# Power.net
KiCad netlist of a schematic drawn in Altium Designer
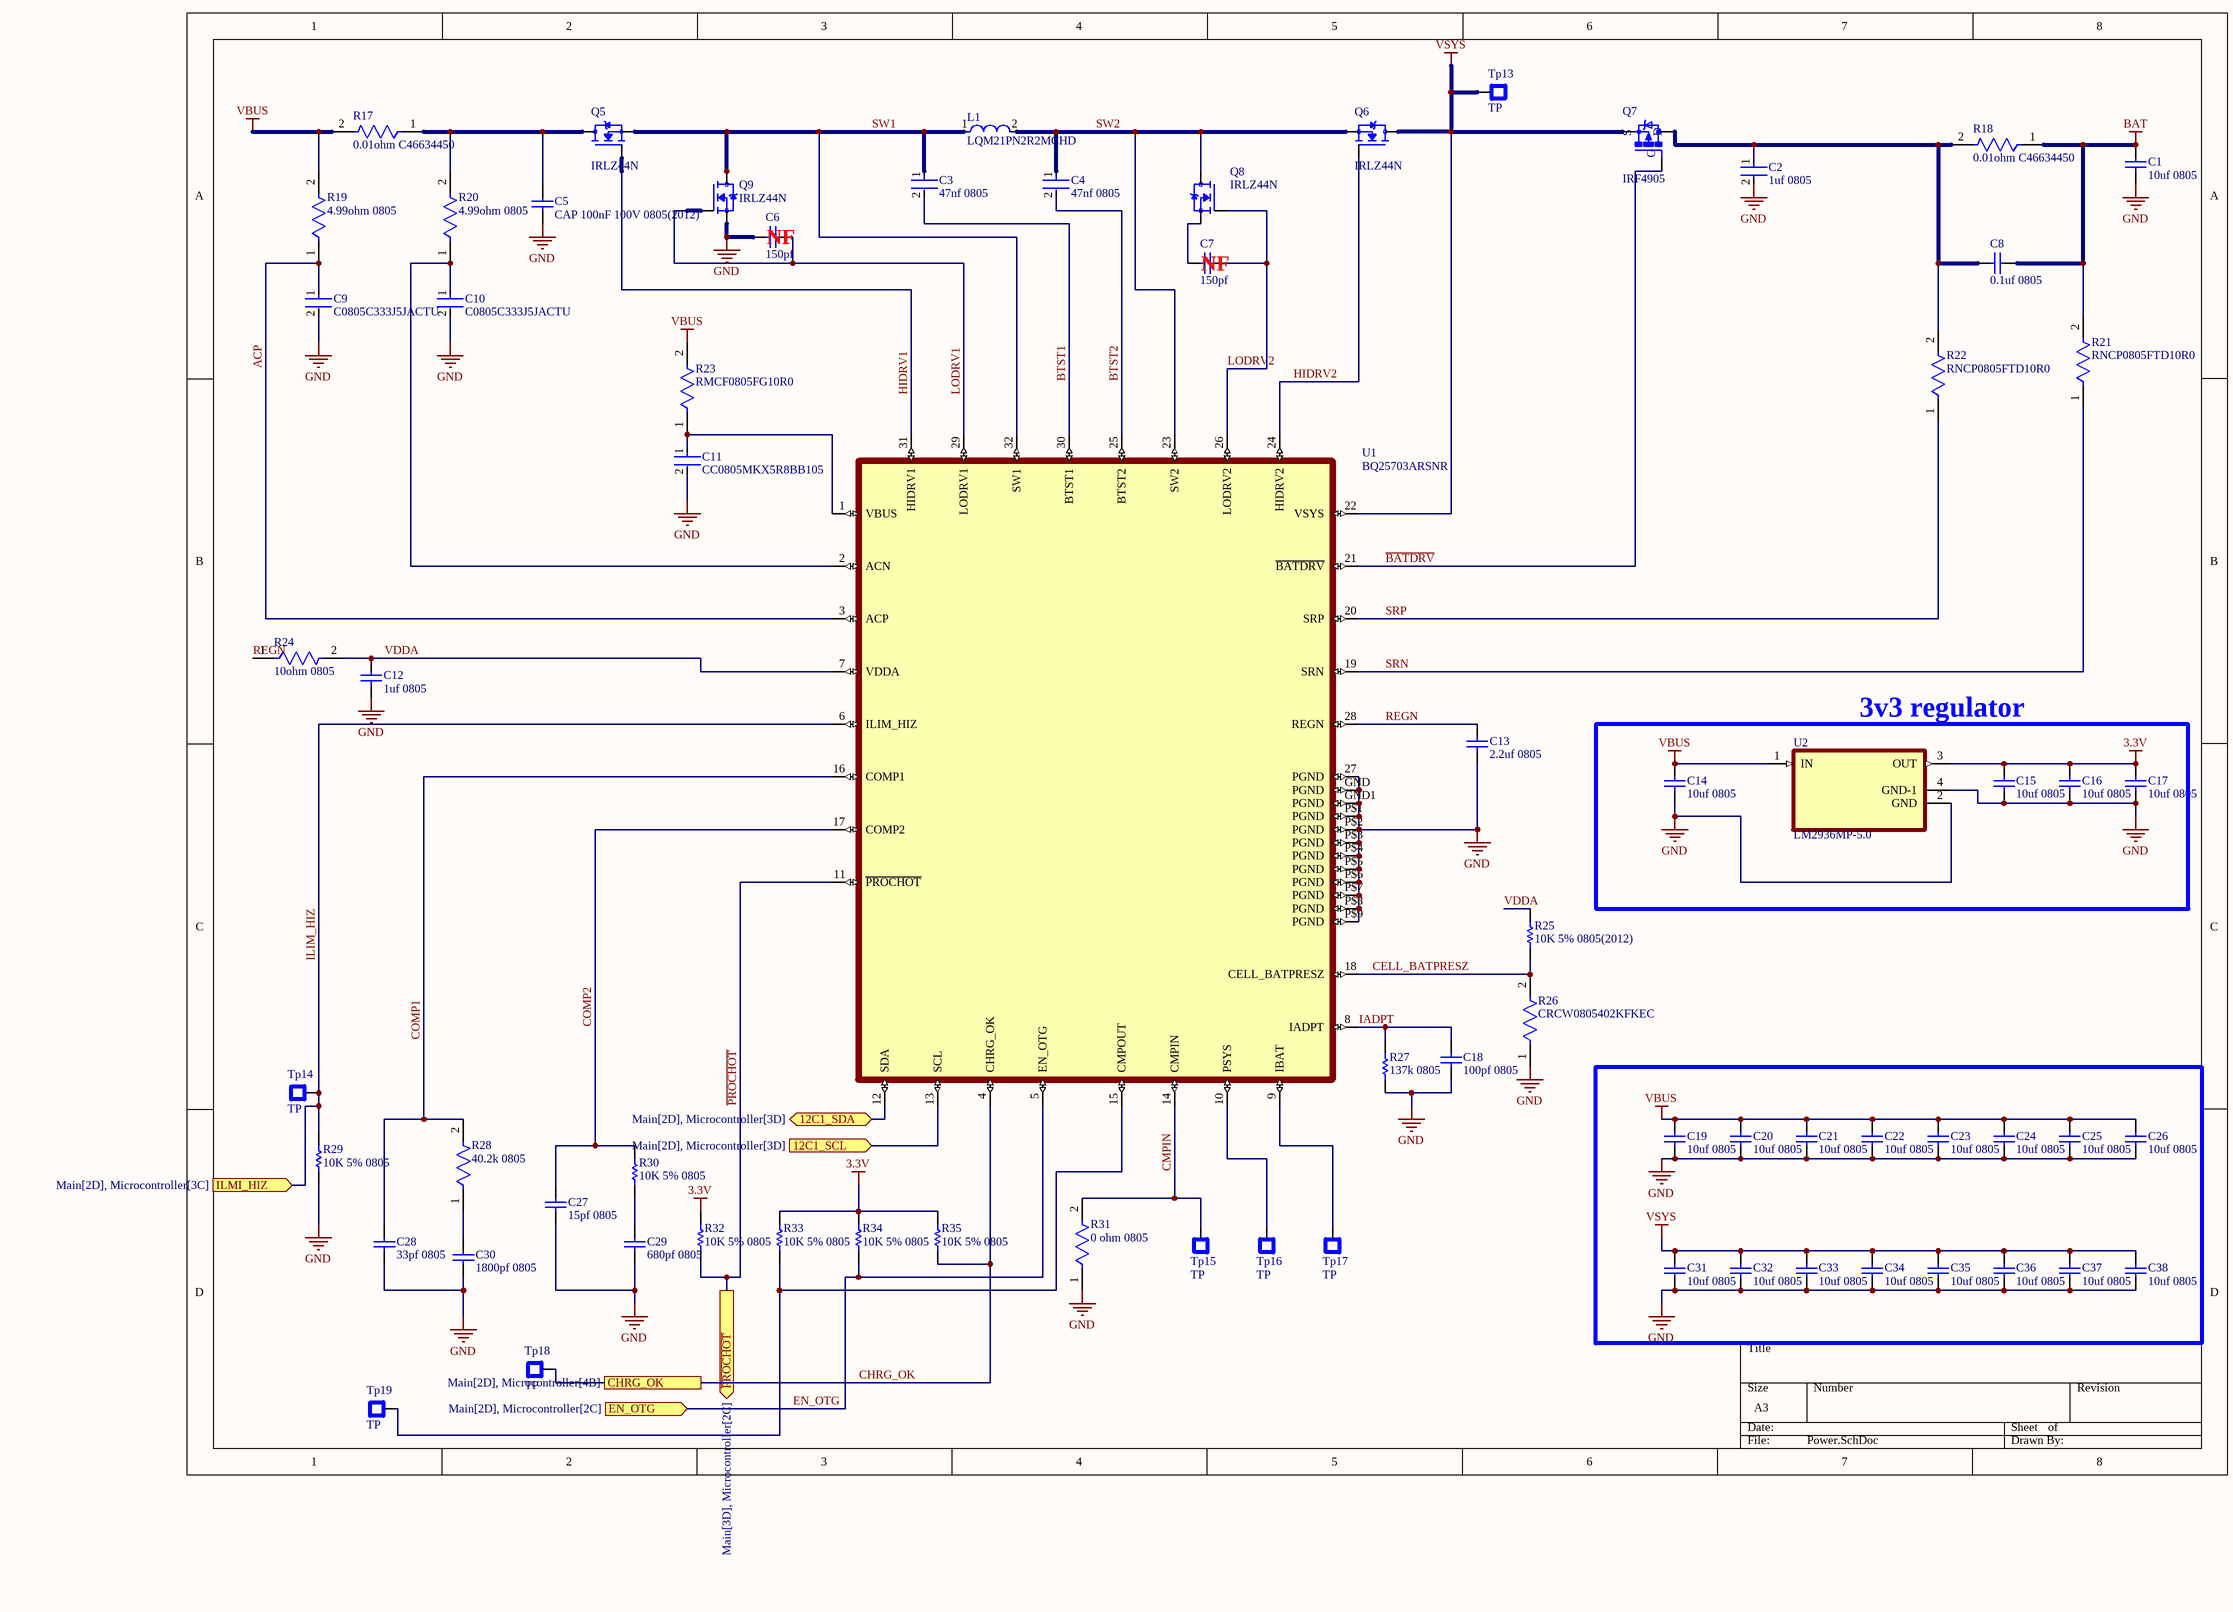
[diagram p0: Power.SchDoc]

(export (version "E")
  (design (tool "Eeschema 10.0.6"))
  (components
    (comp (ref "C1")
      (value "10uf 0805")
      (footprint "CAPC2013X140X50ML20T25")
      (fields
        (field (name "MANUFACTURER") "AVX Interconnect / Elco")
        (field (name "PART NUMBER") "0805ZC106KAT2A")
      )
      (libsource (lib "Altium Content Vault") (part "CAP"))
    )
    (comp (ref "C2")
      (value "1uf 0805")
      (footprint "FP-0805-L_2_01_0_2-W_1_25-MFG")
      (description "08051C105K4T2A Cap Ceramic 1uF 100V X7R 10% Pad SMD 0805 125C Automotive T/R")
      (fields (field (name "TOLERANCE") "10%"))
      (libsource (lib "Altium Content Vault") (part "b4654b650e69147ec39a6b967a45e02"))
    )
    (comp (ref "C3")
      (value "47nf 0805")
      (footprint "FP-C0805C-DN-MFG")
      (description "CAP CER 0.047UF 50V X7R 0805")
      (fields (field (name "TOLERANCE") "0.1") (field (name "MANUFACTURER") "KEMET"))
      (libsource (lib "Altium Content Vault") (part "b4654b650e69147ec39a6b967a45e02"))
    )
    (comp (ref "C4")
      (value "47nf 0805")
      (footprint "FP-C0805C-DN-MFG")
      (description "CAP CER 0.047UF 50V X7R 0805")
      (fields (field (name "TOLERANCE") "0.1") (field (name "MANUFACTURER") "KEMET"))
      (libsource (lib "Altium Content Vault") (part "b4654b650e69147ec39a6b967a45e02"))
    )
    (comp (ref "C5")
      (value "CAP 100nF 100V 0805(2012)")
      (footprint "CAPC0805(2012)145_M")
      (description "CAP 100nF 100V ±10% 0805 (2012 Metric) Thickness 1.45mm SMD")
      (fields (field (name "TOLERANCE") "Â±10%"))
      (libsource (lib "Altium Content Vault") (part "CAP"))
    )
    (comp (ref "C6")
      (value "150pf")
      (footprint "CAPC2013X145X48NL20T23")
      (fields (field (name "PART NUMBER") "VJ0805A151JXAMC") (field (name "MANUFACTURER") "Vitramon"))
      (libsource (lib "Altium Content Vault") (part "CAP"))
    )
    (comp (ref "C7")
      (value "150pf")
      (footprint "CAPC2013X145X48NL20T23")
      (fields (field (name "PART NUMBER") "VJ0805A151JXAMC") (field (name "MANUFACTURER") "Vitramon"))
      (libsource (lib "Altium Content Vault") (part "CAP"))
    )
    (comp (ref "C8")
      (value "0.1uf 0805")
      (footprint "CAPC2013X140X50ML20T25")
      (fields
        (field (name "PART NUMBER") "0805DD104KAT2A")
        (field (name "MANUFACTURER") "AVX Interconnect / Elco")
      )
      (libsource (lib "Altium Content Vault") (part "CAP"))
    )
    (comp (ref "C9")
      (value "C0805C333J5JACTU")
      (footprint "FP-C0805C-DN-MFG")
      (description "CAP CER 0.033UF 50V U2J 0805")
      (fields
        (field (name "MANUFACTURER") "KEMET")
        (field (name "OCTOPART") "https://octopart.com/c0805c333j5jactu-kemet-74774612")
      )
      (libsource (lib "Altium Content Vault") (part "b4654b650e69147ec39a6b967a45e02"))
    )
    (comp (ref "C10")
      (value "C0805C333J5JACTU")
      (footprint "FP-C0805C-DN-MFG")
      (description "CAP CER 0.033UF 50V U2J 0805")
      (fields
        (field (name "MANUFACTURER") "KEMET")
        (field (name "OCTOPART") "https://octopart.com/c0805c333j5jactu-kemet-74774612")
      )
      (libsource (lib "Altium Content Vault") (part "b4654b650e69147ec39a6b967a45e02"))
    )
    (comp (ref "C11")
      (value "CC0805MKX5R8BB105")
      (footprint "FP-CC0805-0_85-MFG")
      (description "CAP CER 1UF 25V X5R 0805")
      (fields
        (field (name "MANUFACTURER") "Yageo")
        (field (name "OCTOPART") "https://octopart.com/cc0805mkx5r8bb105-yageo-81932645")
      )
      (libsource (lib "Altium Content Vault") (part "11868f565c42a9108669ba33697ecf6"))
    )
    (comp (ref "C12")
      (value "1uf 0805")
      (footprint "CAPC2013X145X50NL20T20")
      (fields (field (name "PART NUMBER") "VJ0805Y105KXQRW1BC") (field (name "MANUFACTURER") "Vitramon"))
      (libsource (lib "Altium Content Vault") (part "CAP"))
    )
    (comp (ref "C13")
      (value "2.2uf 0805")
      (footprint "CAPC2013X100X50ML20T25")
      (fields (field (name "PART NUMBER") "C0805C225M4PACTU") (field (name "MANUFACTURER") "Kemet"))
      (libsource (lib "Altium Content Vault") (part "CAP"))
    )
    (comp (ref "C14")
      (value "10uf 0805")
      (footprint "CAPC2013X140X50ML20T25")
      (fields
        (field (name "MANUFACTURER") "AVX Interconnect / Elco")
        (field (name "PART NUMBER") "0805ZC106KAT2A")
      )
      (libsource (lib "Altium Content Vault") (part "CAP"))
    )
    (comp (ref "C15")
      (value "10uf 0805")
      (footprint "CAPC2013X140X50ML20T25")
      (fields
        (field (name "MANUFACTURER") "AVX Interconnect / Elco")
        (field (name "PART NUMBER") "0805ZC106KAT2A")
      )
      (libsource (lib "Altium Content Vault") (part "CAP"))
    )
    (comp (ref "C16")
      (value "10uf 0805")
      (footprint "CAPC2013X140X50ML20T25")
      (fields
        (field (name "MANUFACTURER") "AVX Interconnect / Elco")
        (field (name "PART NUMBER") "0805ZC106KAT2A")
      )
      (libsource (lib "Altium Content Vault") (part "CAP"))
    )
    (comp (ref "C17")
      (value "10uf 0805")
      (footprint "CAPC2013X140X50ML20T25")
      (fields
        (field (name "MANUFACTURER") "AVX Interconnect / Elco")
        (field (name "PART NUMBER") "0805ZC106KAT2A")
      )
      (libsource (lib "Altium Content Vault") (part "CAP"))
    )
    (comp (ref "C18")
      (value "100pf 0805")
      (footprint "CAPC2013X127X50NL20T25")
      (fields
        (field (name "PART NUMBER") "08052C101KAT2A")
        (field (name "MANUFACTURER") "AVX Interconnect / Elco")
      )
      (libsource (lib "Altium Content Vault") (part "CAP"))
    )
    (comp (ref "C19")
      (value "10uf 0805")
      (footprint "CAPC2013X140X50ML20T25")
      (fields
        (field (name "MANUFACTURER") "AVX Interconnect / Elco")
        (field (name "PART NUMBER") "0805ZC106KAT2A")
      )
      (libsource (lib "Altium Content Vault") (part "CAP"))
    )
    (comp (ref "C20")
      (value "10uf 0805")
      (footprint "CAPC2013X140X50ML20T25")
      (fields
        (field (name "MANUFACTURER") "AVX Interconnect / Elco")
        (field (name "PART NUMBER") "0805ZC106KAT2A")
      )
      (libsource (lib "Altium Content Vault") (part "CAP"))
    )
    (comp (ref "C21")
      (value "10uf 0805")
      (footprint "CAPC2013X140X50ML20T25")
      (fields
        (field (name "MANUFACTURER") "AVX Interconnect / Elco")
        (field (name "PART NUMBER") "0805ZC106KAT2A")
      )
      (libsource (lib "Altium Content Vault") (part "CAP"))
    )
    (comp (ref "C22")
      (value "10uf 0805")
      (footprint "CAPC2013X140X50ML20T25")
      (fields
        (field (name "MANUFACTURER") "AVX Interconnect / Elco")
        (field (name "PART NUMBER") "0805ZC106KAT2A")
      )
      (libsource (lib "Altium Content Vault") (part "CAP"))
    )
    (comp (ref "C23")
      (value "10uf 0805")
      (footprint "CAPC2013X140X50ML20T25")
      (fields
        (field (name "MANUFACTURER") "AVX Interconnect / Elco")
        (field (name "PART NUMBER") "0805ZC106KAT2A")
      )
      (libsource (lib "Altium Content Vault") (part "CAP"))
    )
    (comp (ref "C24")
      (value "10uf 0805")
      (footprint "CAPC2013X140X50ML20T25")
      (fields
        (field (name "MANUFACTURER") "AVX Interconnect / Elco")
        (field (name "PART NUMBER") "0805ZC106KAT2A")
      )
      (libsource (lib "Altium Content Vault") (part "CAP"))
    )
    (comp (ref "C25")
      (value "10uf 0805")
      (footprint "CAPC2013X140X50ML20T25")
      (fields
        (field (name "MANUFACTURER") "AVX Interconnect / Elco")
        (field (name "PART NUMBER") "0805ZC106KAT2A")
      )
      (libsource (lib "Altium Content Vault") (part "CAP"))
    )
    (comp (ref "C26")
      (value "10uf 0805")
      (footprint "CAPC2013X140X50ML20T25")
      (fields
        (field (name "MANUFACTURER") "AVX Interconnect / Elco")
        (field (name "PART NUMBER") "0805ZC106KAT2A")
      )
      (libsource (lib "Altium Content Vault") (part "CAP"))
    )
    (comp (ref "C27")
      (value "15pf 0805")
      (footprint "CAPC2013X94X50LL20T25")
      (fields
        (field (name "PART NUMBER") "08051A150KAT2A")
        (field (name "MANUFACTURER") "AVX Interconnect / Elco")
      )
      (libsource (lib "Altium Content Vault") (part "CAP"))
    )
    (comp (ref "C28")
      (value "33pf 0805")
      (footprint "CAPC2013X145X48LL20T23")
      (fields (field (name "PART NUMBER") "VJ0805A330JXBAC") (field (name "MANUFACTURER") "Vitramon"))
      (libsource (lib "Altium Content Vault") (part "CAP"))
    )
    (comp (ref "C29")
      (value "680pf 0805")
      (footprint "CAPC0805(2012)145_L")
      (description "CAP 680pF 100V ±10% 0805 (2012 Metric) Thickness 1.45mm SMD")
      (fields (field (name "TOLERANCE") "Â±10%"))
      (libsource (lib "Altium Content Vault") (part "CAP"))
    )
    (comp (ref "C30")
      (value "1800pf 0805")
      (footprint "CAPC2013X145X48ML20T23")
      (fields (field (name "PART NUMBER") "VJ0805A182FXAMT") (field (name "MANUFACTURER") "Vitramon"))
      (libsource (lib "Altium Content Vault") (part "CAP"))
    )
    (comp (ref "C31")
      (value "10uf 0805")
      (footprint "CAPC2013X140X50ML20T25")
      (fields
        (field (name "MANUFACTURER") "AVX Interconnect / Elco")
        (field (name "PART NUMBER") "0805ZC106KAT2A")
      )
      (libsource (lib "Altium Content Vault") (part "CAP"))
    )
    (comp (ref "C32")
      (value "10uf 0805")
      (footprint "CAPC2013X140X50ML20T25")
      (fields
        (field (name "MANUFACTURER") "AVX Interconnect / Elco")
        (field (name "PART NUMBER") "0805ZC106KAT2A")
      )
      (libsource (lib "Altium Content Vault") (part "CAP"))
    )
    (comp (ref "C33")
      (value "10uf 0805")
      (footprint "CAPC2013X140X50ML20T25")
      (fields
        (field (name "MANUFACTURER") "AVX Interconnect / Elco")
        (field (name "PART NUMBER") "0805ZC106KAT2A")
      )
      (libsource (lib "Altium Content Vault") (part "CAP"))
    )
    (comp (ref "C34")
      (value "10uf 0805")
      (footprint "CAPC2013X140X50ML20T25")
      (fields
        (field (name "MANUFACTURER") "AVX Interconnect / Elco")
        (field (name "PART NUMBER") "0805ZC106KAT2A")
      )
      (libsource (lib "Altium Content Vault") (part "CAP"))
    )
    (comp (ref "C35")
      (value "10uf 0805")
      (footprint "CAPC2013X140X50ML20T25")
      (fields
        (field (name "MANUFACTURER") "AVX Interconnect / Elco")
        (field (name "PART NUMBER") "0805ZC106KAT2A")
      )
      (libsource (lib "Altium Content Vault") (part "CAP"))
    )
    (comp (ref "C36")
      (value "10uf 0805")
      (footprint "CAPC2013X140X50ML20T25")
      (fields
        (field (name "MANUFACTURER") "AVX Interconnect / Elco")
        (field (name "PART NUMBER") "0805ZC106KAT2A")
      )
      (libsource (lib "Altium Content Vault") (part "CAP"))
    )
    (comp (ref "C37")
      (value "10uf 0805")
      (footprint "CAPC2013X140X50ML20T25")
      (fields
        (field (name "MANUFACTURER") "AVX Interconnect / Elco")
        (field (name "PART NUMBER") "0805ZC106KAT2A")
      )
      (libsource (lib "Altium Content Vault") (part "CAP"))
    )
    (comp (ref "C38")
      (value "10uf 0805")
      (footprint "CAPC2013X140X50ML20T25")
      (fields
        (field (name "MANUFACTURER") "AVX Interconnect / Elco")
        (field (name "PART NUMBER") "0805ZC106KAT2A")
      )
      (libsource (lib "Altium Content Vault") (part "CAP"))
    )
    (comp (ref "L1")
      (value "LQM21PN2R2MCHD")
      (footprint "FP-LQM21PN_CH-IPC_C")
      (description "Multilayer Type Inductor for Power Lines, 2012, 2.2μH, 20%, 0.25Ω, 1.3A")
      (libsource (lib "Altium Content Vault") (part "725321dda6339637d4d059423bc1c3c"))
    )
    (comp (ref "Q5")
      (value "IRLZ44N")
      (footprint "TO254P1054X469X1930-3")
      (description "N-Channel 55 V 47A (Tc) 3.8W (Ta), 110W (Tc) Surface Mount D2PAK")
      (fields (field (name "MF") "Infineon / IR"))
      (libsource (lib "power_schi") (part "IRLZ44N"))
    )
    (comp (ref "Q6")
      (value "IRLZ44N")
      (footprint "TO254P1054X469X1930-3")
      (description "N-Channel 55 V 47A (Tc) 3.8W (Ta), 110W (Tc) Surface Mount D2PAK")
      (fields (field (name "MF") "Infineon / IR"))
      (libsource (lib "power_schi") (part "IRLZ44N"))
    )
    (comp (ref "Q7")
      (value "IRF4905")
      (footprint "TO220BH")
      (description "P-Channel 55 V 74A (Tc) 200W (Tc) Through Hole TO-220AB")
      (fields (field (name "MF") "Infineon / IR"))
      (libsource (lib "power_schi") (part "IRF4905"))
    )
    (comp (ref "Q8")
      (value "IRLZ44N")
      (footprint "TO254P1054X469X1930-3")
      (description "N-Channel 55 V 47A (Tc) 3.8W (Ta), 110W (Tc) Surface Mount D2PAK")
      (fields (field (name "MF") "Infineon / IR"))
      (libsource (lib "power_schi") (part "IRLZ44N"))
    )
    (comp (ref "Q9")
      (value "IRLZ44N")
      (footprint "TO254P1054X469X1930-3")
      (description "N-Channel 55 V 47A (Tc) 3.8W (Ta), 110W (Tc) Surface Mount D2PAK")
      (fields (field (name "MF") "Infineon / IR"))
      (libsource (lib "power_schi") (part "IRLZ44N"))
    )
    (comp (ref "R17")
      (value "0.01ohm C46634450")
      (footprint "FP-CRCW0805-HPe3-MFG")
      (description "RES Thick Film, 4.99Ω, 0.5%, 0.5W, 100ppm/°C, 0805")
      (libsource (lib "Altium Content Vault") (part "1029c3af85768c4190bb7ad29bc67b5"))
    )
    (comp (ref "R18")
      (value "0.01ohm C46634450")
      (footprint "FP-CRCW0805-HPe3-MFG")
      (description "RES Thick Film, 4.99Ω, 0.5%, 0.5W, 100ppm/°C, 0805")
      (libsource (lib "Altium Content Vault") (part "1029c3af85768c4190bb7ad29bc67b5"))
    )
    (comp (ref "R19")
      (value "4.99ohm 0805")
      (footprint "FP-CRCW0805-HPe3-MFG")
      (description "RES Thick Film, 4.99Ω, 0.5%, 0.5W, 100ppm/°C, 0805")
      (libsource (lib "Altium Content Vault") (part "1029c3af85768c4190bb7ad29bc67b5"))
    )
    (comp (ref "R20")
      (value "4.99ohm 0805")
      (footprint "FP-CRCW0805-HPe3-MFG")
      (description "RES Thick Film, 4.99Ω, 0.5%, 0.5W, 100ppm/°C, 0805")
      (libsource (lib "Altium Content Vault") (part "1029c3af85768c4190bb7ad29bc67b5"))
    )
    (comp (ref "R21")
      (value "RNCP0805FTD10R0")
      (footprint "FP-RNCP0805-IPC_C")
      (description "10Ω ±1% 0.25W 0805 High Power Anti-Sulfur Thin Film Chip Resistor")
      (fields (field (name "TOLERANCE") "1%"))
      (libsource (lib "Altium Content Vault") (part "1029c3af85768c4190bb7ad29bc67b5"))
    )
    (comp (ref "R22")
      (value "RNCP0805FTD10R0")
      (footprint "FP-RNCP0805-IPC_C")
      (description "10Ω ±1% 0.25W 0805 High Power Anti-Sulfur Thin Film Chip Resistor")
      (fields (field (name "TOLERANCE") "1%"))
      (libsource (lib "Altium Content Vault") (part "1029c3af85768c4190bb7ad29bc67b5"))
    )
    (comp (ref "R23")
      (value "RMCF0805FG10R0")
      (footprint "FP-RMCF0805-IPC_B")
      (description "10Ω ±1% 0.125W 0805 Thick Film Chip Resistor AEC-Q200 compliant")
      (fields (field (name "TOLERANCE") "1%"))
      (libsource (lib "Altium Content Vault") (part "1029c3af85768c4190bb7ad29bc67b5"))
    )
    (comp (ref "R24")
      (value "10ohm 0805")
      (footprint "FP-RMCF0805-IPC_B")
      (description "10Ω ±1% 0.125W 0805 Thick Film Chip Resistor AEC-Q200 compliant")
      (fields (field (name "TOLERANCE") "1%"))
      (libsource (lib "Altium Content Vault") (part "1029c3af85768c4190bb7ad29bc67b5"))
    )
    (comp (ref "R25")
      (value "10K 5% 0805(2012)")
      (footprint "RESC0805(2012)_L")
      (description "10K 0.125W 5% 0805 (2012 Metric)  SMD")
      (fields (field (name "POWER") "0.125 W") (field (name "TOLERANCE") "5 %"))
      (libsource (lib "Altium Content Vault") (part "RES"))
    )
    (comp (ref "R26")
      (value "CRCW0805402KFKEC")
      (footprint "FP-CRCW0805-e3-IPC_B")
      (description "RES Thick Film, 402kΩ, 1%, 0.125W, 100ppm/°C, 0805")
      (fields (field (name "TOLERANCE") "1%"))
      (libsource (lib "Altium Content Vault") (part "1029c3af85768c4190bb7ad29bc67b5"))
    )
    (comp (ref "R27")
      (value "137k 0805")
      (footprint "RESC2013X60X35ML10T20")
      (fields (field (name "MANUFACTURER") "Yageo") (field (name "PART NUMBER") "RC0805FR-07137KL"))
      (libsource (lib "Altium Content Vault") (part "RES"))
    )
    (comp (ref "R28")
      (value "40.2k 0805")
      (footprint "FP-ESR10-MFG")
      (description "40.2kΩ ±1% 0.4W 0805 Anti-Surge Chip Resistor AEC-Q200")
      (fields (field (name "TOLERANCE") "1%"))
      (libsource (lib "Altium Content Vault") (part "1029c3af85768c4190bb7ad29bc67b5"))
    )
    (comp (ref "R29")
      (value "10K 5% 0805")
      (footprint "RESC0805(2012)_L")
      (description "10K 0.125W 5% 0805 (2012 Metric)  SMD")
      (fields (field (name "POWER") "0.125 W") (field (name "TOLERANCE") "5 %"))
      (libsource (lib "Altium Content Vault") (part "RES"))
    )
    (comp (ref "R30")
      (value "10K 5% 0805")
      (footprint "RESC0805(2012)_L")
      (description "10K 0.125W 5% 0805 (2012 Metric)  SMD")
      (fields (field (name "POWER") "0.125 W") (field (name "TOLERANCE") "5 %"))
      (libsource (lib "Altium Content Vault") (part "RES"))
    )
    (comp (ref "R31")
      (value "0 ohm 0805")
      (footprint "FP-HCJ0805-MFG")
      (description "RES 0 OHM JUMPER 1/2W 0805")
      (libsource (lib "Altium Content Vault") (part "1029c3af85768c4190bb7ad29bc67b5"))
    )
    (comp (ref "R32")
      (value "10K 5% 0805")
      (footprint "RESC0805(2012)_L")
      (description "10K 0.125W 5% 0805 (2012 Metric)  SMD")
      (fields (field (name "POWER") "0.125 W") (field (name "TOLERANCE") "5 %"))
      (libsource (lib "Altium Content Vault") (part "RES"))
    )
    (comp (ref "R33")
      (value "10K 5% 0805")
      (footprint "RESC0805(2012)_L")
      (description "10K 0.125W 5% 0805 (2012 Metric)  SMD")
      (fields (field (name "POWER") "0.125 W") (field (name "TOLERANCE") "5 %"))
      (libsource (lib "Altium Content Vault") (part "RES"))
    )
    (comp (ref "R34")
      (value "10K 5% 0805")
      (footprint "RESC0805(2012)_L")
      (description "10K 0.125W 5% 0805 (2012 Metric)  SMD")
      (fields (field (name "POWER") "0.125 W") (field (name "TOLERANCE") "5 %"))
      (libsource (lib "Altium Content Vault") (part "RES"))
    )
    (comp (ref "R35")
      (value "10K 5% 0805")
      (footprint "RESC0805(2012)_L")
      (description "10K 0.125W 5% 0805 (2012 Metric)  SMD")
      (fields (field (name "POWER") "0.125 W") (field (name "TOLERANCE") "5 %"))
      (libsource (lib "Altium Content Vault") (part "RES"))
    )
    (comp (ref "Tp13") (value "TP") (footprint "Tp") (libsource (lib "power_schi") (part "TP")))
    (comp (ref "Tp14") (value "TP") (footprint "Tp") (libsource (lib "power_schi") (part "TP")))
    (comp (ref "Tp15") (value "TP") (footprint "Tp") (libsource (lib "power_schi") (part "TP")))
    (comp (ref "Tp16") (value "TP") (footprint "Tp") (libsource (lib "power_schi") (part "TP")))
    (comp (ref "Tp17") (value "TP") (footprint "Tp") (libsource (lib "power_schi") (part "TP")))
    (comp (ref "Tp18") (value "TP") (footprint "Tp") (libsource (lib "power_schi") (part "TP")))
    (comp (ref "Tp19") (value "TP") (footprint "Tp") (libsource (lib "power_schi") (part "TP")))
    (comp (ref "U1")
      (value "BQ25703ARSNR")
      (footprint "BQ25703A_QFN-32")
      (description "MCU 32-bit ARM Cortex M0+ RISC 128KB Flash 1.8V/2.5V/3.3V 48-Pin LQFP Tray")
      (fields (field (name "MF") "Texas Instruments") (field (name "MANUFACTURER") "STMicroelectronics"))
      (libsource (lib "power_schi") (part "BQ25703ARSNR"))
    )
    (comp (ref "U2")
      (value "LM2936MP-5.0")
      (footprint "SOT230P700X180-4N")
      (fields (field (name "MF") "Texas Instruments"))
      (libsource (lib "power_schi") (part "LM2936MP-5.0"))
    )
  )
  (nets
    (net (code "1") (name "/12C1_SCL") (class "Default")
      (node (ref "U1") (pin "13") (pinfunction "SCL_13") (pintype "bidirectional"))
    )
    (net (code "2") (name "/12C1_SDA") (class "Default")
      (node (ref "U1") (pin "12") (pinfunction "SDA_12") (pintype "bidirectional"))
    )
    (net (code "3") (name "/ACP") (class "Default")
      (node (ref "C9") (pin "1") (pinfunction "1_1") (pintype "passive"))
      (node (ref "R19") (pin "1") (pinfunction "1_1") (pintype "passive"))
      (node (ref "U1") (pin "3") (pinfunction "ACP_3") (pintype "bidirectional"))
    )
    (net (code "4") (name "/BTST1") (class "Default")
      (node (ref "C3") (pin "2") (pinfunction "2_2") (pintype "passive"))
      (node (ref "U1") (pin "30") (pinfunction "BTST1_30") (pintype "bidirectional"))
    )
    (net (code "5") (name "/BTST2") (class "Default")
      (node (ref "C4") (pin "2") (pinfunction "2_2") (pintype "passive"))
      (node (ref "U1") (pin "25") (pinfunction "BTST2_25") (pintype "bidirectional"))
    )
    (net (code "6") (name "/CELL_BATPRESZ") (class "Default")
      (node (ref "R25") (pin "1") (pinfunction "1_1") (pintype "passive"))
      (node (ref "R26") (pin "2") (pinfunction "2_2") (pintype "passive"))
      (node (ref "U1") (pin "18") (pinfunction "CELL_BATPRESZ_18") (pintype "bidirectional"))
    )
    (net (code "7") (name "/CHRG_OK") (class "Default")
      (node (ref "R35") (pin "1") (pinfunction "1_1") (pintype "passive"))
      (node (ref "Tp18") (pin "1") (pinfunction "1_1") (pintype "passive"))
      (node (ref "U1") (pin "4") (pinfunction "CHRG_OK_4") (pintype "bidirectional"))
    )
    (net (code "8") (name "/CMPIN") (class "Default")
      (node (ref "R31") (pin "2") (pinfunction "2_2") (pintype "passive"))
      (node (ref "Tp15") (pin "1") (pinfunction "1_1") (pintype "passive"))
      (node (ref "U1") (pin "14") (pinfunction "CMPIN_14") (pintype "bidirectional"))
    )
    (net (code "9") (name "/COMP1") (class "Default")
      (node (ref "C28") (pin "2") (pinfunction "2_2") (pintype "passive"))
      (node (ref "R28") (pin "2") (pinfunction "2_2") (pintype "passive"))
      (node (ref "U1") (pin "16") (pinfunction "COMP1_16") (pintype "bidirectional"))
    )
    (net (code "10") (name "/COMP2") (class "Default")
      (node (ref "C27") (pin "2") (pinfunction "2_2") (pintype "passive"))
      (node (ref "R30") (pin "2") (pinfunction "2_2") (pintype "passive"))
      (node (ref "U1") (pin "17") (pinfunction "COMP2_17") (pintype "bidirectional"))
    )
    (net (code "11") (name "/EN_OTG") (class "Default")
      (node (ref "R34") (pin "1") (pinfunction "1_1") (pintype "passive"))
      (node (ref "U1") (pin "5") (pinfunction "EN_OTG_5") (pintype "bidirectional"))
    )
    (net (code "12") (name "/HIDRV1") (class "Default")
      (node (ref "Q5") (pin "1") (pinfunction "G_1") (pintype "passive"))
      (node (ref "U1") (pin "31") (pinfunction "HIDRV1_31") (pintype "bidirectional"))
    )
    (net (code "13") (name "/HIDRV2") (class "Default")
      (node (ref "Q6") (pin "1") (pinfunction "G_1") (pintype "passive"))
      (node (ref "U1") (pin "24") (pinfunction "HIDRV2_24") (pintype "bidirectional"))
    )
    (net (code "14") (name "/IADPT") (class "Default")
      (node (ref "C18") (pin "2") (pinfunction "2_2") (pintype "passive"))
      (node (ref "R27") (pin "2") (pinfunction "2_2") (pintype "passive"))
      (node (ref "U1") (pin "8") (pinfunction "IADPT_8") (pintype "bidirectional"))
    )
    (net (code "15") (name "/ILIM_HIZ") (class "Default")
      (node (ref "R29") (pin "2") (pinfunction "2_2") (pintype "passive"))
      (node (ref "Tp14") (pin "1") (pinfunction "1_1") (pintype "passive"))
      (node (ref "U1") (pin "6") (pinfunction "ILIM_HIZ_6") (pintype "bidirectional"))
    )
    (net (code "16") (name "/LODRV1") (class "Default")
      (node (ref "C6") (pin "2") (pinfunction "2_2") (pintype "passive"))
      (node (ref "Q9") (pin "1") (pinfunction "G_1") (pintype "passive"))
      (node (ref "U1") (pin "29") (pinfunction "LODRV1_29") (pintype "bidirectional"))
    )
    (net (code "17") (name "/LODRV2") (class "Default")
      (node (ref "C7") (pin "1") (pinfunction "1_1") (pintype "passive"))
      (node (ref "Q8") (pin "1") (pinfunction "G_1") (pintype "passive"))
      (node (ref "U1") (pin "26") (pinfunction "LODRV2_26") (pintype "bidirectional"))
    )
    (net (code "18") (name "/REGN") (class "Default")
      (node (ref "C13") (pin "2") (pinfunction "2_2") (pintype "passive"))
      (node (ref "R24") (pin "1") (pinfunction "1_1") (pintype "passive"))
      (node (ref "U1") (pin "28") (pinfunction "REGN_28") (pintype "bidirectional"))
    )
    (net (code "19") (name "/SRN") (class "Default")
      (node (ref "R21") (pin "1") (pinfunction "1_1") (pintype "passive"))
      (node (ref "U1") (pin "19") (pinfunction "SRN_19") (pintype "bidirectional"))
    )
    (net (code "20") (name "/SRP") (class "Default")
      (node (ref "R22") (pin "1") (pinfunction "1_1") (pintype "passive"))
      (node (ref "U1") (pin "20") (pinfunction "SRP_20") (pintype "bidirectional"))
    )
    (net (code "21") (name "/SW1") (class "Default")
      (node (ref "C3") (pin "1") (pinfunction "1_1") (pintype "passive"))
      (node (ref "L1") (pin "1") (pinfunction "1_1") (pintype "passive"))
      (node (ref "Q5") (pin "3") (pinfunction "S_3") (pintype "passive"))
      (node (ref "Q9") (pin "2") (pinfunction "D_2") (pintype "passive"))
      (node (ref "U1") (pin "32") (pinfunction "SW1_32") (pintype "bidirectional"))
    )
    (net (code "22") (name "/SW2") (class "Default")
      (node (ref "C4") (pin "1") (pinfunction "1_1") (pintype "passive"))
      (node (ref "L1") (pin "2") (pinfunction "2_2") (pintype "passive"))
      (node (ref "Q6") (pin "3") (pinfunction "S_3") (pintype "passive"))
      (node (ref "Q8") (pin "2") (pinfunction "D_2") (pintype "passive"))
      (node (ref "U1") (pin "23") (pinfunction "SW2_23") (pintype "bidirectional"))
    )
    (net (code "23") (name "/VDDA") (class "Default")
      (node (ref "C12") (pin "2") (pinfunction "2_2") (pintype "passive"))
      (node (ref "R24") (pin "2") (pinfunction "2_2") (pintype "passive"))
      (node (ref "R25") (pin "2") (pinfunction "2_2") (pintype "passive"))
      (node (ref "U1") (pin "7") (pinfunction "VDDA_7") (pintype "bidirectional"))
    )
    (net (code "24") (name "/~{BATDRV}") (class "Default")
      (node (ref "Q7") (pin "G") (pinfunction "G_G") (pintype "passive"))
      (node (ref "U1") (pin "21") (pinfunction "~{BATDRV}_21") (pintype "bidirectional"))
    )
    (net (code "25") (name "/~{PROCHOT}") (class "Default")
      (node (ref "R32") (pin "1") (pinfunction "1_1") (pintype "passive"))
      (node (ref "U1") (pin "11") (pinfunction "~{PROCHOT}_11") (pintype "bidirectional"))
    )
    (net (code "26") (name "3.3V") (class "Default")
      (node (ref "C15") (pin "2") (pinfunction "2_2") (pintype "passive"))
      (node (ref "C16") (pin "2") (pinfunction "2_2") (pintype "passive"))
      (node (ref "C17") (pin "2") (pinfunction "2_2") (pintype "passive"))
      (node (ref "R32") (pin "2") (pinfunction "2_2") (pintype "passive"))
      (node (ref "R33") (pin "2") (pinfunction "2_2") (pintype "passive"))
      (node (ref "R34") (pin "2") (pinfunction "2_2") (pintype "passive"))
      (node (ref "R35") (pin "2") (pinfunction "2_2") (pintype "passive"))
      (node (ref "U2") (pin "3") (pinfunction "OUT_3") (pintype "output"))
    )
    (net (code "27") (name "BAT") (class "Default")
      (node (ref "C1") (pin "2") (pinfunction "2_2") (pintype "passive"))
      (node (ref "C8") (pin "1") (pinfunction "1_1") (pintype "passive"))
      (node (ref "R18") (pin "1") (pinfunction "1_1") (pintype "passive"))
      (node (ref "R21") (pin "2") (pinfunction "2_2") (pintype "passive"))
    )
    (net (code "28") (name "GND") (class "Default")
      (node (ref "C1") (pin "1") (pinfunction "1_1") (pintype "passive"))
      (node (ref "C10") (pin "2") (pinfunction "2_2") (pintype "passive"))
      (node (ref "C11") (pin "2") (pinfunction "2_2") (pintype "passive"))
      (node (ref "C12") (pin "1") (pinfunction "1_1") (pintype "passive"))
      (node (ref "C13") (pin "1") (pinfunction "1_1") (pintype "passive"))
      (node (ref "C14") (pin "1") (pinfunction "1_1") (pintype "passive"))
      (node (ref "C15") (pin "1") (pinfunction "1_1") (pintype "passive"))
      (node (ref "C16") (pin "1") (pinfunction "1_1") (pintype "passive"))
      (node (ref "C17") (pin "1") (pinfunction "1_1") (pintype "passive"))
      (node (ref "C18") (pin "1") (pinfunction "1_1") (pintype "passive"))
      (node (ref "C19") (pin "1") (pinfunction "1_1") (pintype "passive"))
      (node (ref "C2") (pin "2") (pinfunction "2_2") (pintype "passive"))
      (node (ref "C20") (pin "1") (pinfunction "1_1") (pintype "passive"))
      (node (ref "C21") (pin "1") (pinfunction "1_1") (pintype "passive"))
      (node (ref "C22") (pin "1") (pinfunction "1_1") (pintype "passive"))
      (node (ref "C23") (pin "1") (pinfunction "1_1") (pintype "passive"))
      (node (ref "C24") (pin "1") (pinfunction "1_1") (pintype "passive"))
      (node (ref "C25") (pin "1") (pinfunction "1_1") (pintype "passive"))
      (node (ref "C26") (pin "1") (pinfunction "1_1") (pintype "passive"))
      (node (ref "C27") (pin "1") (pinfunction "1_1") (pintype "passive"))
      (node (ref "C28") (pin "1") (pinfunction "1_1") (pintype "passive"))
      (node (ref "C29") (pin "1") (pinfunction "1_1") (pintype "passive"))
      (node (ref "C30") (pin "1") (pinfunction "1_1") (pintype "passive"))
      (node (ref "C31") (pin "1") (pinfunction "1_1") (pintype "passive"))
      (node (ref "C32") (pin "1") (pinfunction "1_1") (pintype "passive"))
      (node (ref "C33") (pin "1") (pinfunction "1_1") (pintype "passive"))
      (node (ref "C34") (pin "1") (pinfunction "1_1") (pintype "passive"))
      (node (ref "C35") (pin "1") (pinfunction "1_1") (pintype "passive"))
      (node (ref "C36") (pin "1") (pinfunction "1_1") (pintype "passive"))
      (node (ref "C37") (pin "1") (pinfunction "1_1") (pintype "passive"))
      (node (ref "C38") (pin "1") (pinfunction "1_1") (pintype "passive"))
      (node (ref "C5") (pin "1") (pinfunction "1_1") (pintype "passive"))
      (node (ref "C6") (pin "1") (pinfunction "1_1") (pintype "passive"))
      (node (ref "C9") (pin "2") (pinfunction "2_2") (pintype "passive"))
      (node (ref "Q9") (pin "3") (pinfunction "S_3") (pintype "passive"))
      (node (ref "R26") (pin "1") (pinfunction "1_1") (pintype "passive"))
      (node (ref "R27") (pin "1") (pinfunction "1_1") (pintype "passive"))
      (node (ref "R29") (pin "1") (pinfunction "1_1") (pintype "passive"))
      (node (ref "R31") (pin "1") (pinfunction "1_1") (pintype "passive"))
      (node (ref "U1") (pin "27") (pinfunction "PGND_27") (pintype "bidirectional"))
      (node (ref "U1") (pin "GND") (pinfunction "PGND_GND") (pintype "bidirectional"))
      (node (ref "U1") (pin "GND1") (pinfunction "PGND_GND1") (pintype "bidirectional"))
      (node (ref "U1") (pin "P$1") (pinfunction "PGND_P$1") (pintype "bidirectional"))
      (node (ref "U1") (pin "P$2") (pinfunction "PGND_P$2") (pintype "bidirectional"))
      (node (ref "U1") (pin "P$3") (pinfunction "PGND_P$3") (pintype "bidirectional"))
      (node (ref "U1") (pin "P$4") (pinfunction "PGND_P$4") (pintype "bidirectional"))
      (node (ref "U1") (pin "P$5") (pinfunction "PGND_P$5") (pintype "bidirectional"))
      (node (ref "U1") (pin "P$6") (pinfunction "PGND_P$6") (pintype "bidirectional"))
      (node (ref "U1") (pin "P$7") (pinfunction "PGND_P$7") (pintype "bidirectional"))
      (node (ref "U1") (pin "P$8") (pinfunction "PGND_P$8") (pintype "bidirectional"))
      (node (ref "U1") (pin "P$9") (pinfunction "PGND_P$9") (pintype "bidirectional"))
      (node (ref "U2") (pin "2") (pinfunction "GND_2") (pintype "power_in"))
      (node (ref "U2") (pin "4") (pinfunction "GND-1_4") (pintype "power_in"))
    )
    (net (code "29") (name "Net-(C2-Pad1)") (class "Default")
      (node (ref "C2") (pin "1") (pinfunction "1_1") (pintype "passive"))
      (node (ref "C8") (pin "2") (pinfunction "2_2") (pintype "passive"))
      (node (ref "Q7") (pin "D") (pinfunction "D_D") (pintype "passive"))
      (node (ref "R18") (pin "2") (pinfunction "2_2") (pintype "passive"))
      (node (ref "R22") (pin "2") (pinfunction "2_2") (pintype "passive"))
    )
    (net (code "30") (name "Net-(C29-Pad2)") (class "Default")
      (node (ref "C29") (pin "2") (pinfunction "2_2") (pintype "passive"))
      (node (ref "R30") (pin "1") (pinfunction "1_1") (pintype "passive"))
    )
    (net (code "31") (name "Net-(C30-Pad2)") (class "Default")
      (node (ref "C30") (pin "2") (pinfunction "2_2") (pintype "passive"))
      (node (ref "R28") (pin "1") (pinfunction "1_1") (pintype "passive"))
    )
    (net (code "32") (name "Net-(Q5-D)") (class "Default")
      (node (ref "C5") (pin "2") (pinfunction "2_2") (pintype "passive"))
      (node (ref "Q5") (pin "2") (pinfunction "D_2") (pintype "passive"))
      (node (ref "R17") (pin "1") (pinfunction "1_1") (pintype "passive"))
      (node (ref "R20") (pin "2") (pinfunction "2_2") (pintype "passive"))
    )
    (net (code "33") (name "Net-(Q8-S)") (class "Default")
      (node (ref "C7") (pin "2") (pinfunction "2_2") (pintype "passive"))
      (node (ref "Q8") (pin "3") (pinfunction "S_3") (pintype "passive"))
    )
    (net (code "34") (name "Net-(U1-ACN)") (class "Default")
      (node (ref "C10") (pin "1") (pinfunction "1_1") (pintype "passive"))
      (node (ref "R20") (pin "1") (pinfunction "1_1") (pintype "passive"))
      (node (ref "U1") (pin "2") (pinfunction "ACN_2") (pintype "bidirectional"))
    )
    (net (code "35") (name "Net-(U1-CMPOUT)") (class "Default")
      (node (ref "R33") (pin "1") (pinfunction "1_1") (pintype "passive"))
      (node (ref "Tp19") (pin "1") (pinfunction "1_1") (pintype "passive"))
      (node (ref "U1") (pin "15") (pinfunction "CMPOUT_15") (pintype "bidirectional"))
    )
    (net (code "36") (name "Net-(U1-IBAT)") (class "Default")
      (node (ref "Tp17") (pin "1") (pinfunction "1_1") (pintype "passive"))
      (node (ref "U1") (pin "9") (pinfunction "IBAT_9") (pintype "bidirectional"))
    )
    (net (code "37") (name "Net-(U1-PSYS)") (class "Default")
      (node (ref "Tp16") (pin "1") (pinfunction "1_1") (pintype "passive"))
      (node (ref "U1") (pin "10") (pinfunction "PSYS_10") (pintype "bidirectional"))
    )
    (net (code "38") (name "Net-(U1-VBUS)") (class "Default")
      (node (ref "C11") (pin "1") (pinfunction "1_1") (pintype "passive"))
      (node (ref "R23") (pin "1") (pinfunction "1_1") (pintype "passive"))
      (node (ref "U1") (pin "1") (pinfunction "VBUS_1") (pintype "bidirectional"))
    )
    (net (code "39") (name "VBUS") (class "Default")
      (node (ref "C14") (pin "2") (pinfunction "2_2") (pintype "passive"))
      (node (ref "C19") (pin "2") (pinfunction "2_2") (pintype "passive"))
      (node (ref "C20") (pin "2") (pinfunction "2_2") (pintype "passive"))
      (node (ref "C21") (pin "2") (pinfunction "2_2") (pintype "passive"))
      (node (ref "C22") (pin "2") (pinfunction "2_2") (pintype "passive"))
      (node (ref "C23") (pin "2") (pinfunction "2_2") (pintype "passive"))
      (node (ref "C24") (pin "2") (pinfunction "2_2") (pintype "passive"))
      (node (ref "C25") (pin "2") (pinfunction "2_2") (pintype "passive"))
      (node (ref "C26") (pin "2") (pinfunction "2_2") (pintype "passive"))
      (node (ref "R17") (pin "2") (pinfunction "2_2") (pintype "passive"))
      (node (ref "R19") (pin "2") (pinfunction "2_2") (pintype "passive"))
      (node (ref "R23") (pin "2") (pinfunction "2_2") (pintype "passive"))
      (node (ref "U2") (pin "1") (pinfunction "IN_1") (pintype "input"))
    )
    (net (code "40") (name "VSYS") (class "Default")
      (node (ref "C31") (pin "2") (pinfunction "2_2") (pintype "passive"))
      (node (ref "C32") (pin "2") (pinfunction "2_2") (pintype "passive"))
      (node (ref "C33") (pin "2") (pinfunction "2_2") (pintype "passive"))
      (node (ref "C34") (pin "2") (pinfunction "2_2") (pintype "passive"))
      (node (ref "C35") (pin "2") (pinfunction "2_2") (pintype "passive"))
      (node (ref "C36") (pin "2") (pinfunction "2_2") (pintype "passive"))
      (node (ref "C37") (pin "2") (pinfunction "2_2") (pintype "passive"))
      (node (ref "C38") (pin "2") (pinfunction "2_2") (pintype "passive"))
      (node (ref "Q6") (pin "2") (pinfunction "D_2") (pintype "passive"))
      (node (ref "Q7") (pin "S") (pinfunction "S_S") (pintype "passive"))
      (node (ref "Tp13") (pin "1") (pinfunction "1_1") (pintype "passive"))
      (node (ref "U1") (pin "22") (pinfunction "VSYS_22") (pintype "bidirectional"))
    )
  )
)
